# Heizoel_Fuellstand.net
KiCad netlist of a schematic drawn in EasyEDA
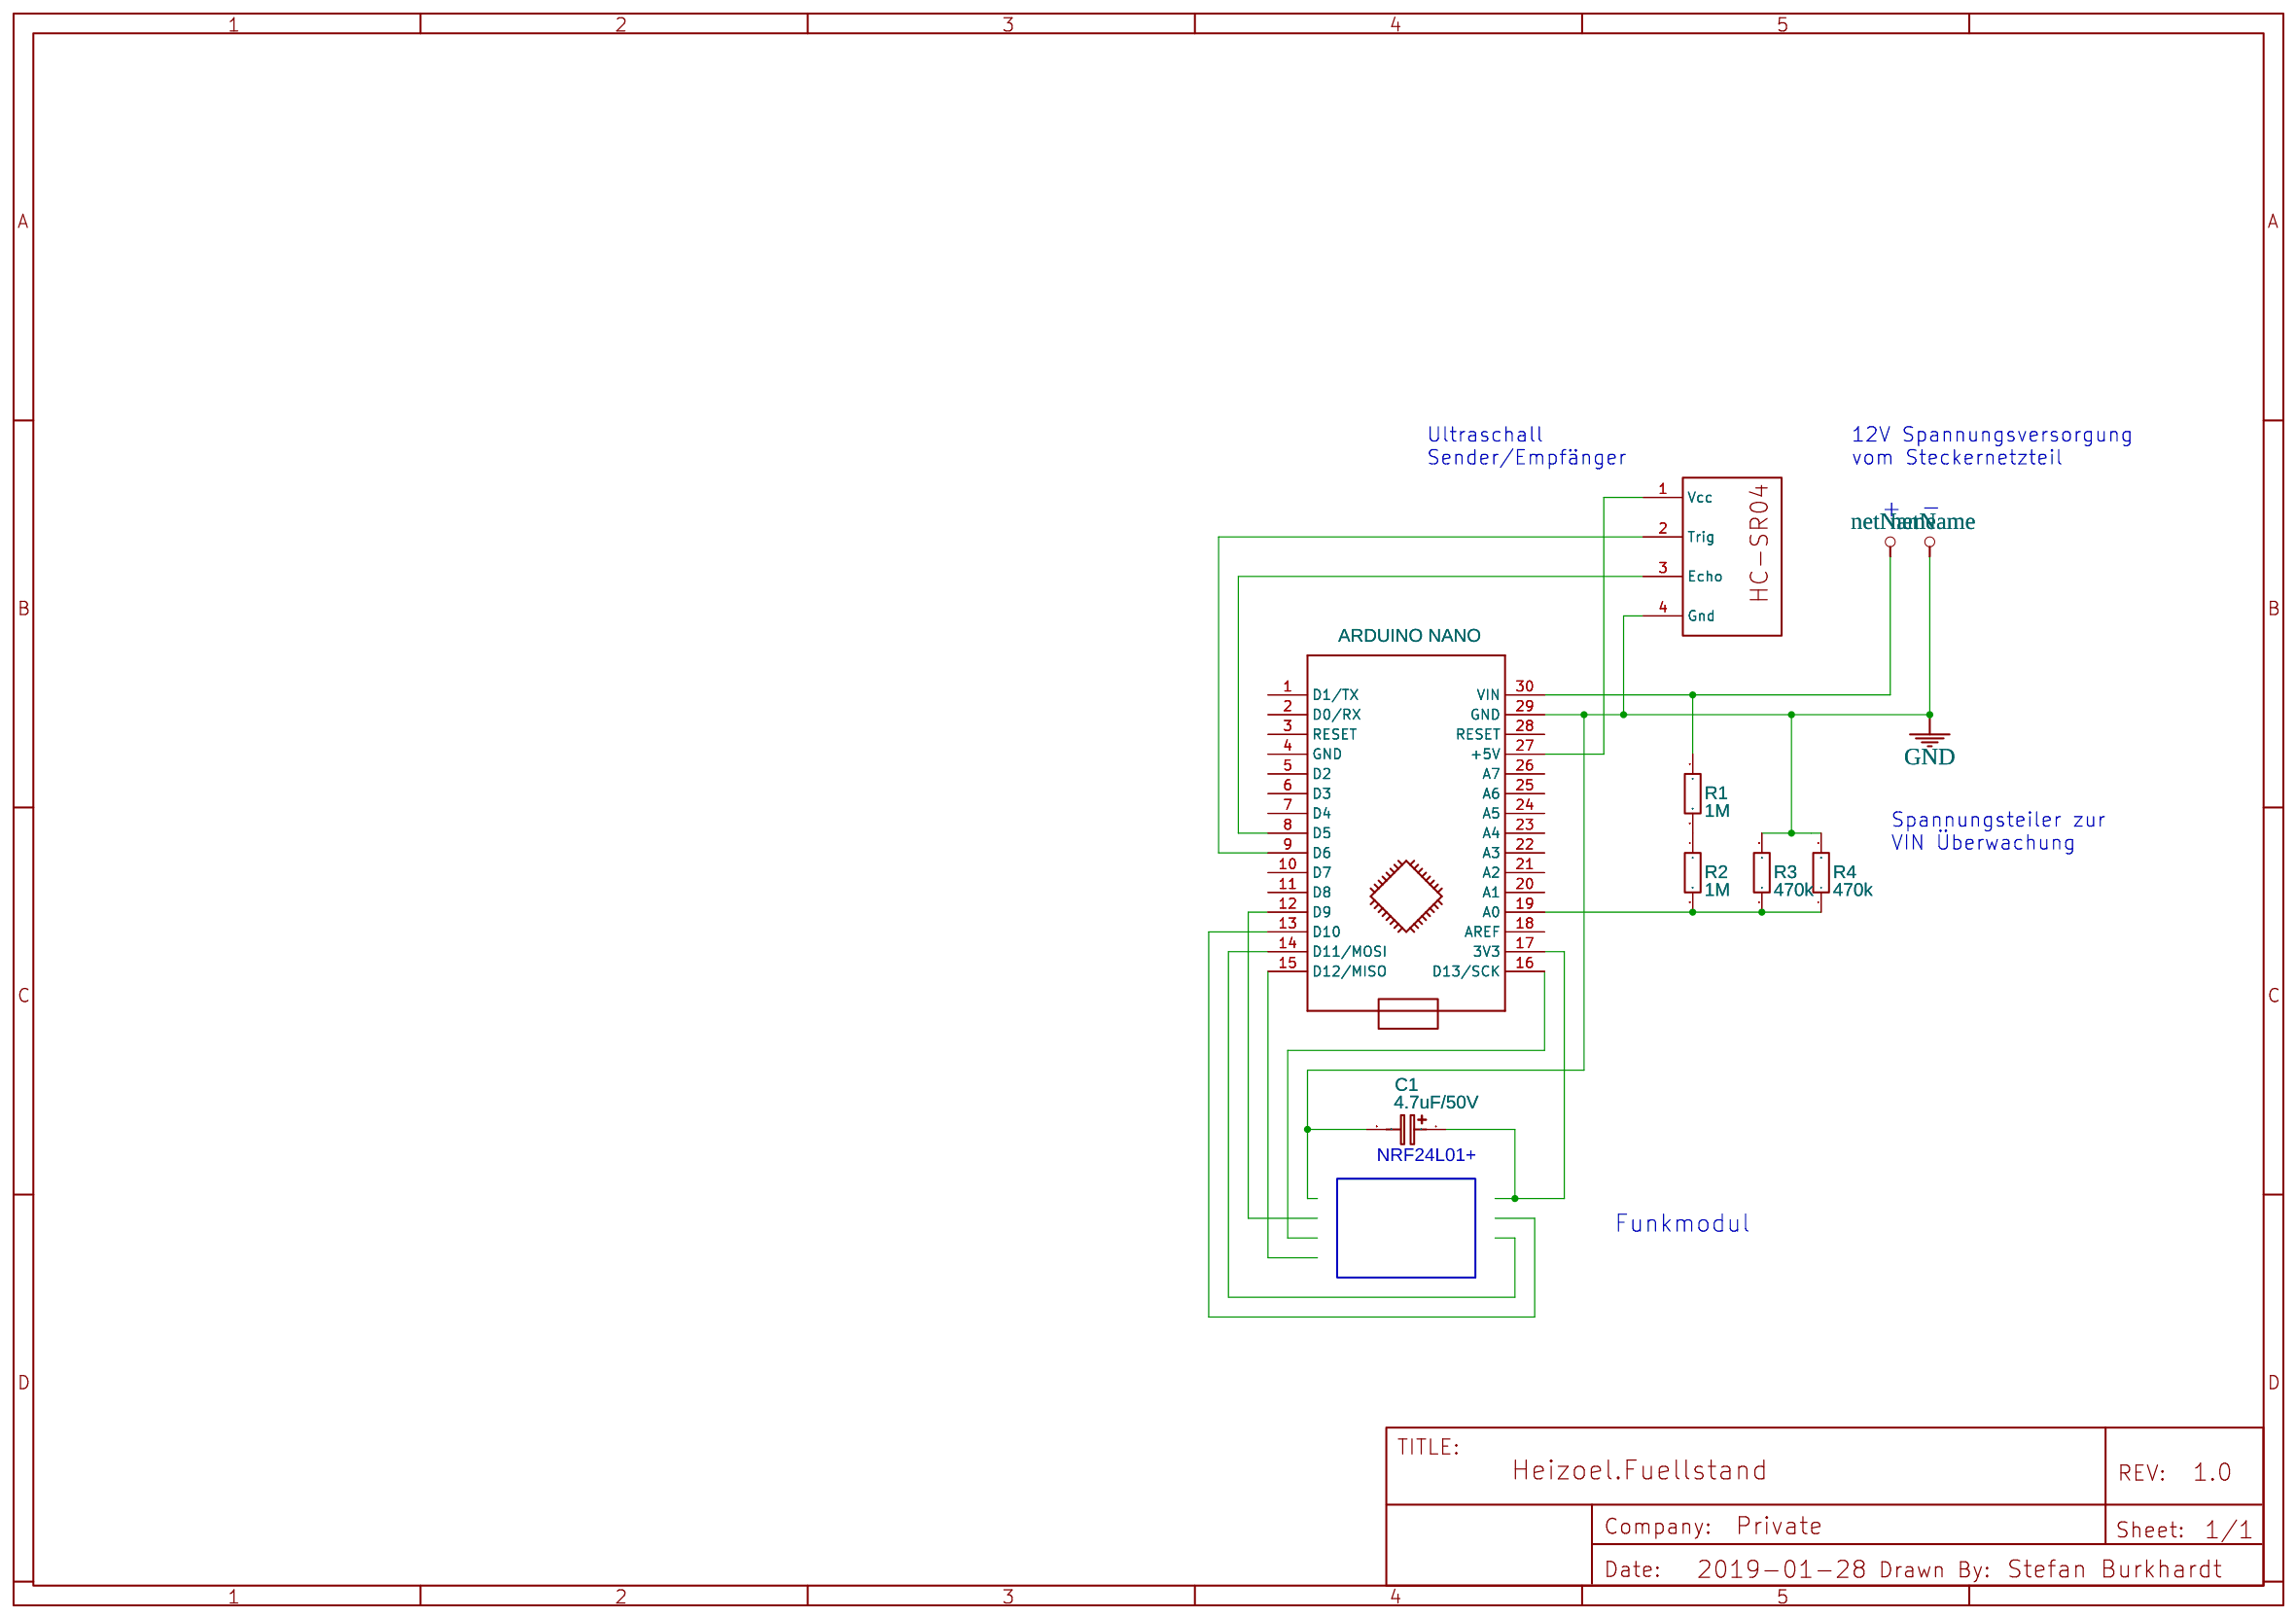
[diagram p0: schematic sheet]

(export (version "E")
  (design (tool "Eeschema 10.0.6"))
  (components
    (comp (ref "C1")
      (value "4.7uF/50V")
      (fields (field (name "BOM_Manufacturer Part") "?"))
      (libsource (lib "") (part "Cap_Electrolytic(TH)_D3.0XF1.5_EU"))
    )
    (comp (ref "R1")
      (value "1M")
      (fields (field (name "BOM_Manufacturer Part") "?"))
      (libsource (lib "") (part "Res_AXIAL-0.3(1/8W)_EU"))
    )
    (comp (ref "R2")
      (value "1M")
      (fields (field (name "BOM_Manufacturer Part") "?"))
      (libsource (lib "") (part "Res_AXIAL-0.3(1/8W)_EU"))
    )
    (comp (ref "R3")
      (value "470k")
      (fields (field (name "BOM_Manufacturer Part") "?"))
      (libsource (lib "") (part "Res_AXIAL-0.3(1/8W)_EU_1"))
    )
    (comp (ref "R4")
      (value "470k")
      (fields (field (name "BOM_Manufacturer Part") "?"))
      (libsource (lib "") (part "Res_AXIAL-0.3(1/8W)_EU_1"))
    )
    (comp (ref "U1")
      (value "ARDUINO NANO")
      (fields (field (name "BOM_Manufacturer Part") "?"))
      (libsource (lib "") (part "Unknown_705_420"))
    )
    (comp (ref "U3") (value "HC-SR04") (libsource (lib "") (part "Unknown_895_295")))
  )
  (nets
    (net (code "1") (name "GND") (class "Default")
      (node (ref "C1") (pin "2") (pinfunction "2_2") (pintype "unspecified"))
      (node (ref "R1") (pin "1") (pinfunction "1_1") (pintype "unspecified"))
      (node (ref "R3") (pin "2") (pinfunction "2_2") (pintype "unspecified"))
      (node (ref "R4") (pin "2") (pinfunction "2_2") (pintype "unspecified"))
      (node (ref "U1") (pin "29") (pinfunction "GND_29") (pintype "unspecified"))
      (node (ref "U1") (pin "30") (pinfunction "VIN_30") (pintype "unspecified"))
      (node (ref "U3") (pin "4") (pinfunction "Gnd_4") (pintype "unspecified"))
    )
    (net (code "2") (name "Net-(R1-Pad2)") (class "Default")
      (node (ref "R1") (pin "2") (pinfunction "2_2") (pintype "unspecified"))
      (node (ref "R2") (pin "1") (pinfunction "1_1") (pintype "unspecified"))
    )
    (net (code "3") (name "Net-(U1-+5V)") (class "Default")
      (node (ref "U1") (pin "27") (pinfunction "+5V_27") (pintype "unspecified"))
      (node (ref "U3") (pin "1") (pinfunction "Vcc_1") (pintype "unspecified"))
    )
    (net (code "4") (name "Net-(U1-3V3)") (class "Default")
      (node (ref "C1") (pin "1") (pinfunction "1_1") (pintype "unspecified"))
      (node (ref "U1") (pin "17") (pinfunction "3V3_17") (pintype "unspecified"))
    )
    (net (code "5") (name "Net-(U1-A0)") (class "Default")
      (node (ref "R2") (pin "2") (pinfunction "2_2") (pintype "unspecified"))
      (node (ref "R3") (pin "1") (pinfunction "1_1") (pintype "unspecified"))
      (node (ref "R4") (pin "1") (pinfunction "1_1") (pintype "unspecified"))
      (node (ref "U1") (pin "19") (pinfunction "A0_19") (pintype "unspecified"))
    )
    (net (code "6") (name "Net-(U1-D5)") (class "Default")
      (node (ref "U1") (pin "8") (pinfunction "D5_8") (pintype "unspecified"))
      (node (ref "U3") (pin "3") (pinfunction "Echo_3") (pintype "unspecified"))
    )
    (net (code "7") (name "Net-(U1-D6)") (class "Default")
      (node (ref "U1") (pin "9") (pinfunction "D6_9") (pintype "unspecified"))
      (node (ref "U3") (pin "2") (pinfunction "Trig_2") (pintype "unspecified"))
    )
    (net (code "8") (name "unconnected-(U1-A1-Pad20)") (class "Default")
      (node (ref "U1") (pin "20") (pinfunction "A1_20") (pintype "unspecified"))
    )
    (net (code "9") (name "unconnected-(U1-A2-Pad21)") (class "Default")
      (node (ref "U1") (pin "21") (pinfunction "A2_21") (pintype "unspecified"))
    )
    (net (code "10") (name "unconnected-(U1-A3-Pad22)") (class "Default")
      (node (ref "U1") (pin "22") (pinfunction "A3_22") (pintype "unspecified"))
    )
    (net (code "11") (name "unconnected-(U1-A4-Pad23)") (class "Default")
      (node (ref "U1") (pin "23") (pinfunction "A4_23") (pintype "unspecified"))
    )
    (net (code "12") (name "unconnected-(U1-A5-Pad24)") (class "Default")
      (node (ref "U1") (pin "24") (pinfunction "A5_24") (pintype "unspecified"))
    )
    (net (code "13") (name "unconnected-(U1-A6-Pad25)") (class "Default")
      (node (ref "U1") (pin "25") (pinfunction "A6_25") (pintype "unspecified"))
    )
    (net (code "14") (name "unconnected-(U1-A7-Pad26)") (class "Default")
      (node (ref "U1") (pin "26") (pinfunction "A7_26") (pintype "unspecified"))
    )
    (net (code "15") (name "unconnected-(U1-AREF-Pad18)") (class "Default")
      (node (ref "U1") (pin "18") (pinfunction "AREF_18") (pintype "unspecified"))
    )
    (net (code "16") (name "unconnected-(U1-D0{slash}RX-Pad2)") (class "Default")
      (node (ref "U1") (pin "2") (pinfunction "D0/RX_2") (pintype "unspecified"))
    )
    (net (code "17") (name "unconnected-(U1-D1{slash}TX-Pad1)") (class "Default")
      (node (ref "U1") (pin "1") (pinfunction "D1/TX_1") (pintype "unspecified"))
    )
    (net (code "18") (name "unconnected-(U1-D2-Pad5)") (class "Default")
      (node (ref "U1") (pin "5") (pinfunction "D2_5") (pintype "unspecified"))
    )
    (net (code "19") (name "unconnected-(U1-D3-Pad6)") (class "Default")
      (node (ref "U1") (pin "6") (pinfunction "D3_6") (pintype "unspecified"))
    )
    (net (code "20") (name "unconnected-(U1-D4-Pad7)") (class "Default")
      (node (ref "U1") (pin "7") (pinfunction "D4_7") (pintype "unspecified"))
    )
    (net (code "21") (name "unconnected-(U1-D7-Pad10)") (class "Default")
      (node (ref "U1") (pin "10") (pinfunction "D7_10") (pintype "unspecified"))
    )
    (net (code "22") (name "unconnected-(U1-D8-Pad11)") (class "Default")
      (node (ref "U1") (pin "11") (pinfunction "D8_11") (pintype "unspecified"))
    )
    (net (code "23") (name "unconnected-(U1-D9-Pad12)") (class "Default")
      (node (ref "U1") (pin "12") (pinfunction "D9_12") (pintype "unspecified"))
    )
    (net (code "24") (name "unconnected-(U1-D10-Pad13)") (class "Default")
      (node (ref "U1") (pin "13") (pinfunction "D10_13") (pintype "unspecified"))
    )
    (net (code "25") (name "unconnected-(U1-D11{slash}MOSI-Pad14)") (class "Default")
      (node (ref "U1") (pin "14") (pinfunction "D11/MOSI_14") (pintype "unspecified"))
    )
    (net (code "26") (name "unconnected-(U1-D12{slash}MISO-Pad15)") (class "Default")
      (node (ref "U1") (pin "15") (pinfunction "D12/MISO_15") (pintype "unspecified"))
    )
    (net (code "27") (name "unconnected-(U1-D13{slash}SCK-Pad16)") (class "Default")
      (node (ref "U1") (pin "16") (pinfunction "D13/SCK_16") (pintype "unspecified"))
    )
    (net (code "28") (name "unconnected-(U1-GND-Pad4)") (class "Default")
      (node (ref "U1") (pin "4") (pinfunction "GND_4") (pintype "unspecified"))
    )
    (net (code "29") (name "unconnected-(U1-RESET-Pad3)") (class "Default")
      (node (ref "U1") (pin "3") (pinfunction "RESET_3") (pintype "unspecified"))
    )
    (net (code "30") (name "unconnected-(U1-RESET-Pad28)") (class "Default")
      (node (ref "U1") (pin "28") (pinfunction "RESET_28") (pintype "unspecified"))
    )
  )
)
